# ESP32-SCH.net
KiCad netlist of a schematic drawn in Altium Designer
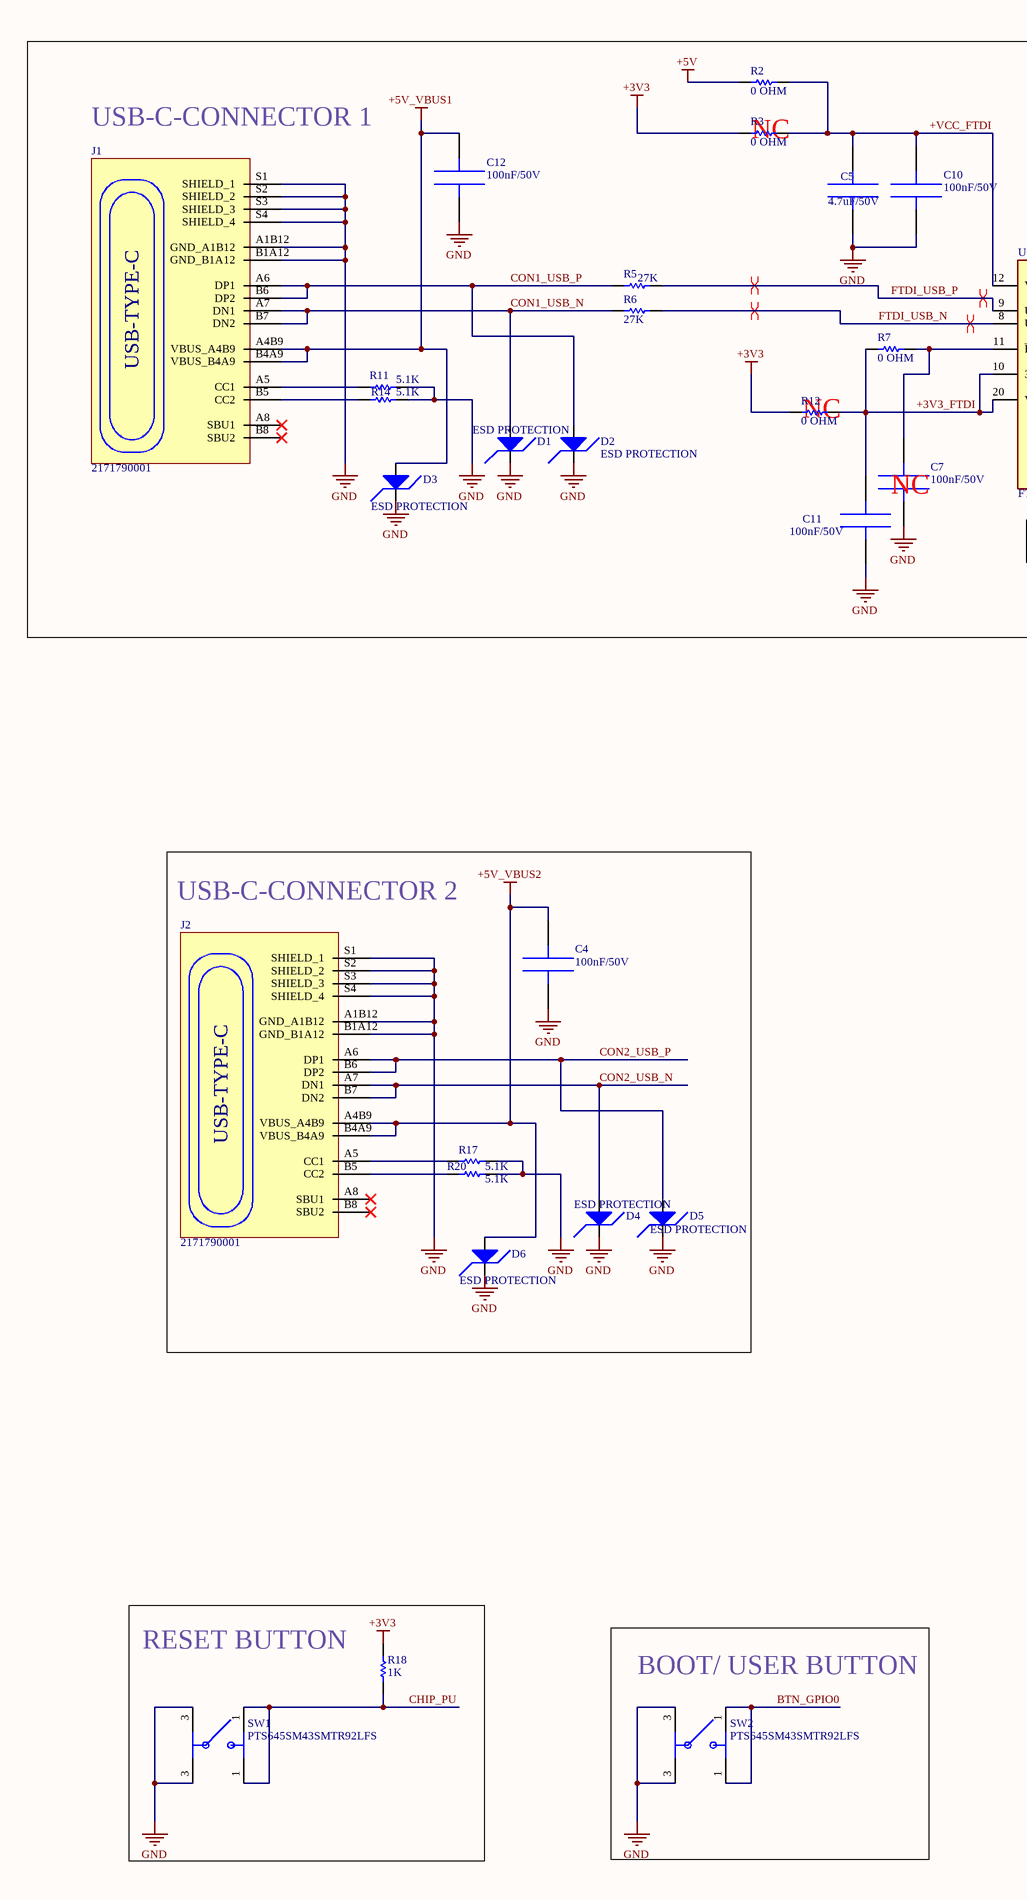
[diagram p0: ESP32-SCH.SchDoc, left]
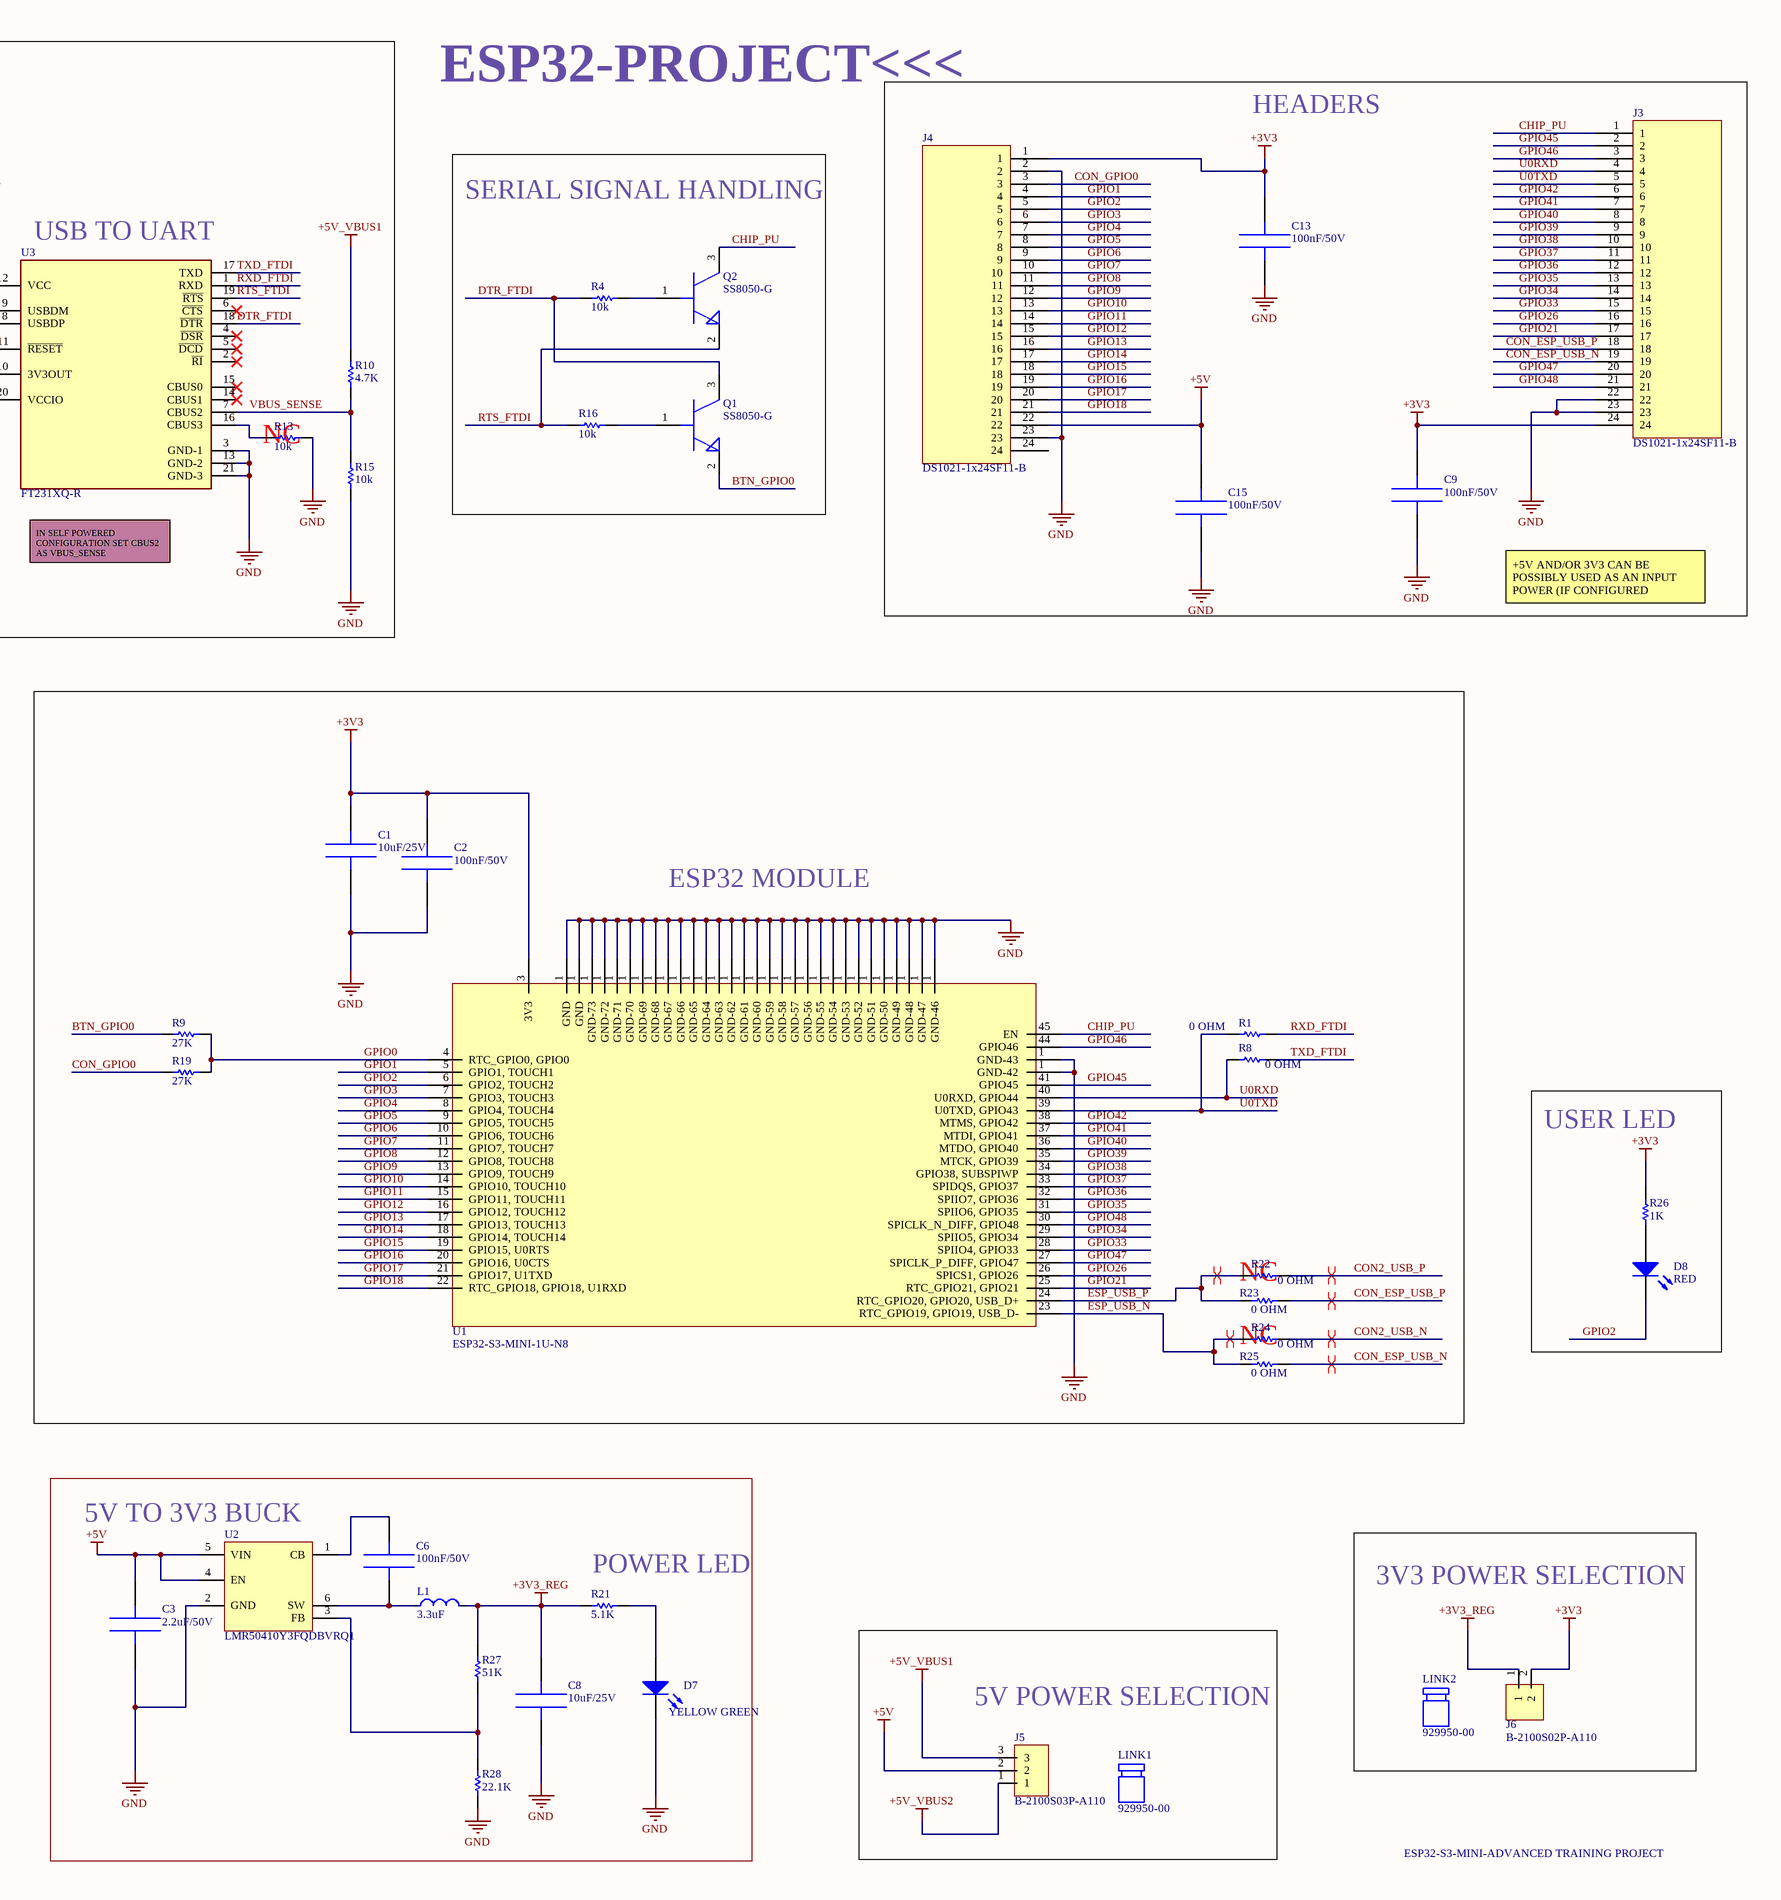
[diagram p1: ESP32-SCH.SchDoc, right]

(export (version "E")
  (design (tool "Eeschema 10.0.6"))
  (components
    (comp (ref "C1")
      (value "10uF/25V")
      (footprint "CL05A106MP8NUB8")
      (fields
        (field (name "MANUFACTURER") "Samsung")
        (field (name "MANUFACTURER PART NUMBER") "CL05A106MP8NUB8")
        (field (name "LCSC PART NUMBER") "C307415")
      )
      (libsource (lib "Schlib1") (part "CL05A106MP8NUB8"))
    )
    (comp (ref "C2")
      (value "100nF/50V")
      (footprint "CL05A106MP8NUB8")
      (fields
        (field (name "MANUFACTURER") "Samsung")
        (field (name "MANUFACTURER PART NUMBER") "CL10A105KP8NNNC")
        (field (name "LCSC PART NUMBER") "C14445")
      )
      (libsource (lib "Schlib1") (part "CL10A105KP8NNNC"))
    )
    (comp (ref "C3")
      (value "2.2uF/50V")
      (footprint "CL05A106MP8NUB8")
      (fields
        (field (name "MANUFACTURER") "Samsung")
        (field (name "MANUFACTURER PART NUMBER") "CL10A225KB8NNNC")
        (field (name "LCSC PART NUMBER") "C913904")
      )
      (libsource (lib "Schlib1") (part "CL10A225KB8NNNC"))
    )
    (comp (ref "C4")
      (value "100nF/50V")
      (footprint "CL05A106MP8NUB8")
      (fields
        (field (name "MANUFACTURER") "Samsung")
        (field (name "MANUFACTURER PART NUMBER") "CL10A105KP8NNNC")
        (field (name "LCSC PART NUMBER") "C14445")
      )
      (libsource (lib "Schlib1") (part "CL10A105KP8NNNC"))
    )
    (comp (ref "C5")
      (value "4.7uF/50V")
      (footprint "CC0603KRX7R9BB104")
      (fields
        (field (name "MANUFACTURER") "Yageo")
        (field (name "MANUFACTURER PART NUMBER") "CC0603KRX7R9BB104")
        (field (name "LCSC PART NUMBER") "C14663")
      )
      (libsource (lib "Schlib1") (part "CC0603KRX7R9BB104"))
    )
    (comp (ref "C6")
      (value "100nF/50V")
      (footprint "CL05A106MP8NUB8")
      (fields
        (field (name "MANUFACTURER") "Samsung")
        (field (name "MANUFACTURER PART NUMBER") "CL10A105KP8NNNC")
        (field (name "LCSC PART NUMBER") "C14445")
      )
      (libsource (lib "Schlib1") (part "CL10A105KP8NNNC"))
    )
    (comp (ref "C7")
      (value "100nF/50V")
      (footprint "CL05A106MP8NUB8")
      (fields
        (field (name "MANUFACTURER") "Samsung")
        (field (name "MANUFACTURER PART NUMBER") "CL10A105KP8NNNC")
        (field (name "LCSC PART NUMBER") "C14445")
      )
      (libsource (lib "Schlib1") (part "CL10A105KP8NNNC"))
    )
    (comp (ref "C8")
      (value "10uF/25V")
      (footprint "CL05A106MP8NUB8")
      (fields
        (field (name "MANUFACTURER") "Samsung")
        (field (name "MANUFACTURER PART NUMBER") "CL05A106MP8NUB8")
        (field (name "LCSC PART NUMBER") "C307415")
      )
      (libsource (lib "Schlib1") (part "CL05A106MP8NUB8"))
    )
    (comp (ref "C9")
      (value "100nF/50V")
      (footprint "CL05A106MP8NUB8")
      (fields
        (field (name "MANUFACTURER") "Samsung")
        (field (name "MANUFACTURER PART NUMBER") "CL10A105KP8NNNC")
        (field (name "LCSC PART NUMBER") "C14445")
      )
      (libsource (lib "Schlib1") (part "CL10A105KP8NNNC"))
    )
    (comp (ref "C10")
      (value "100nF/50V")
      (footprint "CL05A106MP8NUB8")
      (fields
        (field (name "MANUFACTURER") "Samsung")
        (field (name "MANUFACTURER PART NUMBER") "CL10A105KP8NNNC")
        (field (name "LCSC PART NUMBER") "C14445")
      )
      (libsource (lib "Schlib1") (part "CL10A105KP8NNNC"))
    )
    (comp (ref "C11")
      (value "100nF/50V")
      (footprint "CL05A106MP8NUB8")
      (fields
        (field (name "MANUFACTURER") "Samsung")
        (field (name "MANUFACTURER PART NUMBER") "CL10A105KP8NNNC")
        (field (name "LCSC PART NUMBER") "C14445")
      )
      (libsource (lib "Schlib1") (part "CL10A105KP8NNNC"))
    )
    (comp (ref "C12")
      (value "100nF/50V")
      (footprint "CL05A106MP8NUB8")
      (fields
        (field (name "MANUFACTURER") "Samsung")
        (field (name "MANUFACTURER PART NUMBER") "CL10A105KP8NNNC")
        (field (name "LCSC PART NUMBER") "C14445")
      )
      (libsource (lib "Schlib1") (part "CL10A105KP8NNNC"))
    )
    (comp (ref "C13")
      (value "100nF/50V")
      (footprint "CL05A106MP8NUB8")
      (fields
        (field (name "MANUFACTURER") "Samsung")
        (field (name "MANUFACTURER PART NUMBER") "CL10A105KP8NNNC")
        (field (name "LCSC PART NUMBER") "C14445")
      )
      (libsource (lib "Schlib1") (part "CL10A105KP8NNNC"))
    )
    (comp (ref "C15")
      (value "100nF/50V")
      (footprint "CL05A106MP8NUB8")
      (fields
        (field (name "MANUFACTURER") "Samsung")
        (field (name "MANUFACTURER PART NUMBER") "CL10A105KP8NNNC")
        (field (name "LCSC PART NUMBER") "C14445")
      )
      (libsource (lib "Schlib1") (part "CL10A105KP8NNNC"))
    )
    (comp (ref "D1")
      (value "ESD PROTECTION")
      (footprint "ESD5Z3.3T1G")
      (description "Trans Voltage Suppressor Diode, 158W, 3.3V V(RWM), Unidirectional, 1 Element, Silicon")
      (fields
        (field (name "MANUFACTURER") "ON Semiconductor")
        (field (name "MANUFACTURER PART NUMBER") "ESD5Z3.3T1G")
      )
      (libsource (lib "Schlib1") (part "ESD5Z3.3T1G"))
    )
    (comp (ref "D2")
      (value "ESD PROTECTION")
      (footprint "ESD5Z3.3T1G")
      (description "Trans Voltage Suppressor Diode, 158W, 3.3V V(RWM), Unidirectional, 1 Element, Silicon")
      (fields
        (field (name "MANUFACTURER") "ON Semiconductor")
        (field (name "MANUFACTURER PART NUMBER") "ESD5Z3.3T1G")
      )
      (libsource (lib "Schlib1") (part "ESD5Z3.3T1G"))
    )
    (comp (ref "D3")
      (value "ESD PROTECTION")
      (footprint "ESD5Z3.3T1G")
      (description "Trans Voltage Suppressor Diode, 158W, 3.3V V(RWM), Unidirectional, 1 Element, Silicon")
      (fields
        (field (name "MANUFACTURER") "ON Semiconductor")
        (field (name "MANUFACTURER PART NUMBER") "ESD5Z3.3T1G")
      )
      (libsource (lib "Schlib1") (part "ESD5Z3.3T1G"))
    )
    (comp (ref "D4")
      (value "ESD PROTECTION")
      (footprint "ESD5Z3.3T1G")
      (description "Trans Voltage Suppressor Diode, 158W, 3.3V V(RWM), Unidirectional, 1 Element, Silicon")
      (fields
        (field (name "MANUFACTURER") "ON Semiconductor")
        (field (name "MANUFACTURER PART NUMBER") "ESD5Z3.3T1G")
      )
      (libsource (lib "Schlib1") (part "ESD5Z3.3T1G"))
    )
    (comp (ref "D5")
      (value "ESD PROTECTION")
      (footprint "ESD5Z3.3T1G")
      (description "Trans Voltage Suppressor Diode, 158W, 3.3V V(RWM), Unidirectional, 1 Element, Silicon")
      (fields
        (field (name "MANUFACTURER") "ON Semiconductor")
        (field (name "MANUFACTURER PART NUMBER") "ESD5Z3.3T1G")
      )
      (libsource (lib "Schlib1") (part "ESD5Z3.3T1G"))
    )
    (comp (ref "D6")
      (value "ESD PROTECTION")
      (footprint "ESD5Z3.3T1G")
      (description "Trans Voltage Suppressor Diode, 158W, 3.3V V(RWM), Unidirectional, 1 Element, Silicon")
      (fields
        (field (name "MANUFACTURER") "ON Semiconductor")
        (field (name "MANUFACTURER PART NUMBER") "ESD5Z3.3T1G")
      )
      (libsource (lib "Schlib1") (part "ESD5Z3.3T1G"))
    )
    (comp (ref "D7")
      (value "YELLOW GREEN")
      (footprint "VLMG1500-GS08")
      (description "Single Color LED, Yellow Green, 0.5mm")
      (fields
        (field (name "MANUFACTURER") "Vishay")
        (field (name "MANUFACTURER PART NUMBER") "VLMG1500-GS08")
      )
      (libsource (lib "Schlib1") (part "VLMG1500-GS08"))
    )
    (comp (ref "D8")
      (value "RED")
      (footprint "VLMG1500-GS08")
      (description "Single Color LED, Super Red, 0.5mm")
      (fields
        (field (name "MANUFACTURER") "Vishay")
        (field (name "MANUFACTURER PART NUMBER") "VLMS1500-GS08")
      )
      (libsource (lib "Schlib1") (part "VLMS1500-GS08"))
    )
    (comp (ref "J1")
      (value "2171790001")
      (footprint "217179-0001")
      (description "USB Type C - Connector, Top-mount SMT, 16pos ¦ Molex Incorporated 217179-0001")
      (fields (field (name "MANUFACTURER") "Molex") (field (name "MANUFACTURER PART NUMBER") "217179-0001"))
      (libsource (lib "Schlib1") (part "217179-0001"))
    )
    (comp (ref "J2")
      (value "2171790001")
      (footprint "217179-0001")
      (description "USB Type C - Connector, Top-mount SMT, 16pos ¦ Molex Incorporated 217179-0001")
      (fields (field (name "MANUFACTURER") "Molex") (field (name "MANUFACTURER PART NUMBER") "217179-0001"))
      (libsource (lib "Schlib1") (part "217179-0001"))
    )
    (comp (ref "J3")
      (value "DS1021-1x24SF11-B")
      (footprint "DS1021-1x24SF11")
      (fields
        (field (name "MANUFACTURER") "Ningbo Connfly Electric")
        (field (name "LCSC PART NUMBER") "C7430380")
      )
      (libsource (lib "Schlib1") (part "DS1021-1x24SF11-B"))
    )
    (comp (ref "J4")
      (value "DS1021-1x24SF11-B")
      (footprint "DS1021-1x24SF11")
      (fields
        (field (name "MANUFACTURER") "Ningbo Connfly Electric")
        (field (name "LCSC PART NUMBER") "C7430380")
      )
      (libsource (lib "") (part "DS1021-1x24SF11-B_1"))
    )
    (comp (ref "J5")
      (value "B-2100S03P-A110")
      (footprint "B-2100S03P-A110")
      (fields (field (name "MANUFACTURER") "CKMTW") (field (name "LCSC PART NUMBER") "C124376"))
      (libsource (lib "Schlib1") (part "B-2100S03P-A110"))
    )
    (comp (ref "J6")
      (value "B-2100S02P-A110")
      (footprint "B-2100S02P-A110")
      (fields (field (name "MANUFACTURER") "CKMTW") (field (name "LCSC PART NUMBER") "C124375"))
      (libsource (lib "Schlib1") (part "B-2100S02P-A110"))
    )
    (comp (ref "L1")
      (value "3.3uF")
      (footprint "MLZ2012N3R3LT000")
      (description "General Purpose Inductor, 3.3uH, 20%, 1 Element, Ferrite-Core, SMD, 0805")
      (fields
        (field (name "MANUFACTURER") "TDK")
        (field (name "MANUFACTURER PART NUMBER") "MLZ2012N3R3LT000")
      )
      (libsource (lib "Schlib1") (part "MLZ2012N3R3LT000"))
    )
    (comp (ref "LINK1")
      (value "929950-00")
      (description "INTERCONNECTION DEVICE")
      (fields (field (name "MANUFACTURER") "3M") (field (name "LCSC PART NUMBER") "C6725179"))
      (libsource (lib "Schlib1") (part "929950-00"))
    )
    (comp (ref "LINK2")
      (value "929950-00")
      (description "INTERCONNECTION DEVICE")
      (fields (field (name "MANUFACTURER") "3M") (field (name "LCSC PART NUMBER") "C6725179"))
      (libsource (lib "Schlib1") (part "929950-00"))
    )
    (comp (ref "Q1")
      (value "SS8050-G")
      (footprint "SS8050-G")
      (description "Small Signal Bipolar Transistor, 1.5A I(C), 25V V(BR)CEO, 1-Element, NPN, Silicon")
      (fields (field (name "MANUFACTURER") "Comchip") (field (name "LCSC PART NUMBER") "C164885"))
      (libsource (lib "Schlib1") (part "SS8050-G"))
    )
    (comp (ref "Q2")
      (value "SS8050-G")
      (footprint "SS8050-G")
      (description "Small Signal Bipolar Transistor, 1.5A I(C), 25V V(BR)CEO, 1-Element, NPN, Silicon")
      (fields (field (name "MANUFACTURER") "Comchip") (field (name "LCSC PART NUMBER") "C164885"))
      (libsource (lib "Schlib1") (part "SS8050-G"))
    )
    (comp (ref "R1")
      (value "0 OHM")
      (footprint "RC0402JR")
      (description "Metal Glaze/thick Film, 0.0625W, 0ohm, Surface Mount, 0402")
      (fields
        (field (name "MANUFACTURER") "Yageo")
        (field (name "MANUFACTURER PART NUMBER") "RC0402JR-070RL")
      )
      (libsource (lib "Schlib1") (part "RC0402JR-070RL"))
    )
    (comp (ref "R2")
      (value "0 OHM")
      (footprint "RC0402JR")
      (description "Metal Glaze/thick Film, 0.0625W, 0ohm, Surface Mount, 0402")
      (fields
        (field (name "MANUFACTURER") "Yageo")
        (field (name "MANUFACTURER PART NUMBER") "RC0402JR-070RL")
      )
      (libsource (lib "Schlib1") (part "RC0402JR-070RL"))
    )
    (comp (ref "R3")
      (value "0 OHM")
      (footprint "RC0402JR")
      (description "Metal Glaze/thick Film, 0.0625W, 0ohm, Surface Mount, 0402")
      (fields
        (field (name "MANUFACTURER") "Yageo")
        (field (name "MANUFACTURER PART NUMBER") "RC0402JR-070RL")
      )
      (libsource (lib "Schlib1") (part "RC0402JR-070RL"))
    )
    (comp (ref "R4")
      (value "10k")
      (footprint "RC0402JR")
      (fields
        (field (name "MANUFACTURER") "Stackpole Electronics")
        (field (name "MANUFACTURER PART NUMBER") "RMCF0402FT10K0")
        (field (name "TOLERANCE") "1%")
      )
      (libsource (lib "Schlib1") (part "RMCF0402FT10K0"))
    )
    (comp (ref "R5")
      (value "27K")
      (footprint "RC0402JR")
      (fields
        (field (name "MANUFACTURER") "Yageo")
        (field (name "MANUFACTURER PART NUMBER") "RC0402JR-0727KL")
        (field (name "TOLERANCE") "5%")
      )
      (libsource (lib "Schlib1") (part "RC0402JR-0727KL"))
    )
    (comp (ref "R6")
      (value "27K")
      (footprint "RC0402JR")
      (fields
        (field (name "MANUFACTURER") "Yageo")
        (field (name "MANUFACTURER PART NUMBER") "RC0402JR-0727KL")
        (field (name "TOLERANCE") "5%")
      )
      (libsource (lib "Schlib1") (part "RC0402JR-0727KL"))
    )
    (comp (ref "R7")
      (value "0 OHM")
      (footprint "RC0402JR")
      (description "Metal Glaze/thick Film, 0.0625W, 0ohm, Surface Mount, 0402")
      (fields
        (field (name "MANUFACTURER") "Yageo")
        (field (name "MANUFACTURER PART NUMBER") "RC0402JR-070RL")
      )
      (libsource (lib "Schlib1") (part "RC0402JR-070RL"))
    )
    (comp (ref "R8")
      (value "0 OHM")
      (footprint "RC0402JR")
      (description "Metal Glaze/thick Film, 0.0625W, 0ohm, Surface Mount, 0402")
      (fields
        (field (name "MANUFACTURER") "Yageo")
        (field (name "MANUFACTURER PART NUMBER") "RC0402JR-070RL")
      )
      (libsource (lib "Schlib1") (part "RC0402JR-070RL"))
    )
    (comp (ref "R9")
      (value "27K")
      (footprint "RC0402JR")
      (fields
        (field (name "MANUFACTURER") "Yageo")
        (field (name "MANUFACTURER PART NUMBER") "RC0402JR-0727KL")
        (field (name "TOLERANCE") "5%")
      )
      (libsource (lib "Schlib1") (part "RC0402JR-0727KL"))
    )
    (comp (ref "R10")
      (value "4.7K")
      (footprint "RC0402JR")
      (fields
        (field (name "MANUFACTURER") "Yageo")
        (field (name "MANUFACTURER PART NUMBER") "RC0402JR-074K7L")
        (field (name "TOLERANCE") "5%")
      )
      (libsource (lib "Schlib1") (part "RC0402JR-074K7L"))
    )
    (comp (ref "R11")
      (value "5.1K")
      (footprint "AC0402FR-075K1L")
      (fields
        (field (name "MANUFACTURER") "Yageo")
        (field (name "MANUFACTURER PART NUMBER") "AC0402FR-075K1L")
        (field (name "TOLERANCE") "1%")
      )
      (libsource (lib "Schlib1") (part "AC0402FR-075K1L"))
    )
    (comp (ref "R12")
      (value "0 OHM")
      (footprint "RC0402JR")
      (description "Metal Glaze/thick Film, 0.0625W, 0ohm, Surface Mount, 0402")
      (fields
        (field (name "MANUFACTURER") "Yageo")
        (field (name "MANUFACTURER PART NUMBER") "RC0402JR-070RL")
      )
      (libsource (lib "Schlib1") (part "RC0402JR-070RL"))
    )
    (comp (ref "R13")
      (value "10k")
      (footprint "RC0402JR")
      (fields
        (field (name "MANUFACTURER") "Stackpole Electronics")
        (field (name "MANUFACTURER PART NUMBER") "RMCF0402FT10K0")
        (field (name "TOLERANCE") "1%")
      )
      (libsource (lib "Schlib1") (part "RMCF0402FT10K0"))
    )
    (comp (ref "R14")
      (value "5.1K")
      (footprint "AC0402FR-075K1L")
      (fields
        (field (name "MANUFACTURER") "Yageo")
        (field (name "MANUFACTURER PART NUMBER") "AC0402FR-075K1L")
        (field (name "TOLERANCE") "1%")
      )
      (libsource (lib "Schlib1") (part "AC0402FR-075K1L"))
    )
    (comp (ref "R15")
      (value "10k")
      (footprint "RC0402JR")
      (fields
        (field (name "MANUFACTURER") "Stackpole Electronics")
        (field (name "MANUFACTURER PART NUMBER") "RMCF0402FT10K0")
        (field (name "TOLERANCE") "1%")
      )
      (libsource (lib "Schlib1") (part "RMCF0402FT10K0"))
    )
    (comp (ref "R16")
      (value "10k")
      (footprint "RC0402JR")
      (fields
        (field (name "MANUFACTURER") "Stackpole Electronics")
        (field (name "MANUFACTURER PART NUMBER") "RMCF0402FT10K0")
        (field (name "TOLERANCE") "1%")
      )
      (libsource (lib "Schlib1") (part "RMCF0402FT10K0"))
    )
    (comp (ref "R17")
      (value "5.1K")
      (footprint "AC0402FR-075K1L")
      (fields
        (field (name "MANUFACTURER") "Yageo")
        (field (name "MANUFACTURER PART NUMBER") "AC0402FR-075K1L")
        (field (name "TOLERANCE") "1%")
      )
      (libsource (lib "Schlib1") (part "AC0402FR-075K1L"))
    )
    (comp (ref "R18")
      (value "1K")
      (footprint "0603WAF1001T5E")
      (fields
        (field (name "MANUFACTURER") "Royal Electronic Factory")
        (field (name "MANUFACTURER PART NUMBER") "0603WAF1001T5E")
        (field (name "LCSC PART NUMBER") "C21190")
      )
      (libsource (lib "Schlib1") (part "0603WAF1001T5E"))
    )
    (comp (ref "R19")
      (value "27K")
      (footprint "RC0402JR")
      (fields
        (field (name "MANUFACTURER") "Yageo")
        (field (name "MANUFACTURER PART NUMBER") "RC0402JR-0727KL")
        (field (name "TOLERANCE") "5%")
      )
      (libsource (lib "Schlib1") (part "RC0402JR-0727KL"))
    )
    (comp (ref "R20")
      (value "5.1K")
      (footprint "AC0402FR-075K1L")
      (fields
        (field (name "MANUFACTURER") "Yageo")
        (field (name "MANUFACTURER PART NUMBER") "AC0402FR-075K1L")
        (field (name "TOLERANCE") "1%")
      )
      (libsource (lib "Schlib1") (part "AC0402FR-075K1L"))
    )
    (comp (ref "R21")
      (value "5.1K")
      (footprint "AC0402FR-075K1L")
      (fields
        (field (name "MANUFACTURER") "Yageo")
        (field (name "MANUFACTURER PART NUMBER") "AC0402FR-075K1L")
        (field (name "TOLERANCE") "1%")
      )
      (libsource (lib "Schlib1") (part "AC0402FR-075K1L"))
    )
    (comp (ref "R22")
      (value "0 OHM")
      (footprint "RC0402JR")
      (description "Metal Glaze/thick Film, 0.0625W, 0ohm, Surface Mount, 0402")
      (fields
        (field (name "MANUFACTURER") "Yageo")
        (field (name "MANUFACTURER PART NUMBER") "RC0402JR-070RL")
      )
      (libsource (lib "Schlib1") (part "RC0402JR-070RL"))
    )
    (comp (ref "R23")
      (value "0 OHM")
      (footprint "RC0402JR")
      (description "Metal Glaze/thick Film, 0.0625W, 0ohm, Surface Mount, 0402")
      (fields
        (field (name "MANUFACTURER") "Yageo")
        (field (name "MANUFACTURER PART NUMBER") "RC0402JR-070RL")
      )
      (libsource (lib "Schlib1") (part "RC0402JR-070RL"))
    )
    (comp (ref "R24")
      (value "0 OHM")
      (footprint "RC0402JR")
      (description "Metal Glaze/thick Film, 0.0625W, 0ohm, Surface Mount, 0402")
      (fields
        (field (name "MANUFACTURER") "Yageo")
        (field (name "MANUFACTURER PART NUMBER") "RC0402JR-070RL")
      )
      (libsource (lib "Schlib1") (part "RC0402JR-070RL"))
    )
    (comp (ref "R25")
      (value "0 OHM")
      (footprint "RC0402JR")
      (description "Metal Glaze/thick Film, 0.0625W, 0ohm, Surface Mount, 0402")
      (fields
        (field (name "MANUFACTURER") "Yageo")
        (field (name "MANUFACTURER PART NUMBER") "RC0402JR-070RL")
      )
      (libsource (lib "Schlib1") (part "RC0402JR-070RL"))
    )
    (comp (ref "R26")
      (value "1K")
      (footprint "0603WAF1001T5E")
      (fields
        (field (name "MANUFACTURER") "Royal Electronic Factory")
        (field (name "MANUFACTURER PART NUMBER") "0603WAF1001T5E")
        (field (name "LCSC PART NUMBER") "C21190")
      )
      (libsource (lib "Schlib1") (part "0603WAF1001T5E"))
    )
    (comp (ref "R27")
      (value "51K")
      (footprint "RC0402JR")
      (fields
        (field (name "MANUFACTURER") "Yageo")
        (field (name "MANUFACTURER PART NUMBER") "RC0402FR-0751KL")
        (field (name "TOLERANCE") "1%")
      )
      (libsource (lib "Schlib1") (part "RC0402FR-0751KL"))
    )
    (comp (ref "R28")
      (value "22.1K")
      (footprint "RC0402JR")
      (fields
        (field (name "MANUFACTURER") "Yageo")
        (field (name "MANUFACTURER PART NUMBER") "RC0402FR-0722K1L")
        (field (name "TOLERANCE") "1%")
      )
      (libsource (lib "Schlib1") (part "RC0402FR-0722K1L"))
    )
    (comp (ref "SW1")
      (value "PTS645SM43SMTR92LFS")
      (footprint "PTS645SM43SMTR92LFS")
      (fields (field (name "MANUFACTURER") "ITT C&K") (field (name "LCSC PART NUMBER") "C221880"))
      (libsource (lib "Schlib1") (part "PTS645SM43SMTR92LFS"))
    )
    (comp (ref "SW2")
      (value "PTS645SM43SMTR92LFS")
      (footprint "PTS645SM43SMTR92LFS")
      (fields (field (name "MANUFACTURER") "ITT C&K") (field (name "LCSC PART NUMBER") "C221880"))
      (libsource (lib "Schlib1") (part "PTS645SM43SMTR92LFS"))
    )
    (comp (ref "U1")
      (value "ESP32-S3-MINI-1U-N8")
      (footprint "ESP32-S3-MINI-1U-N8_1")
      (fields (field (name "MANUFACTURER") "Espressif Systems") (field (name "LCSC PART NUMBER") "C2980299"))
      (libsource (lib "Schlib1") (part "ESP32-S3-MINI-1U-N8_1"))
    )
    (comp (ref "U2")
      (value "LMR50410Y3FQDBVRQ1")
      (footprint "LMR50410Y3FQDBVRQ1")
      (description "Switching Regulator, Current-mode, 1A, 2100kHz Switching Freq-Max, PDSO6")
      (fields (field (name "MANUFACTURER") "Texas Instruments") (field (name "LCSC PART NUMBER") "C5219374"))
      (libsource (lib "Schlib1") (part "LMR50410Y3FQDBVRQ1"))
    )
    (comp (ref "U3")
      (value "FT231XQ-R")
      (footprint "FT231XQ-R")
      (description "Microprocessor Circuit, CMOS")
      (fields (field (name "MANUFACTURER") "FTDI") (field (name "LCSC PART NUMBER") "C132159"))
      (libsource (lib "Schlib1") (part "FT231XQ-R"))
    )
  )
  (nets
    (net (code "1") (name "+3V3") (class "Default")
      (node (ref "C1") (pin "2") (pinfunction "2_2") (pintype "passive"))
      (node (ref "C13") (pin "2") (pinfunction "2_2") (pintype "passive"))
      (node (ref "C2") (pin "2") (pinfunction "2_2") (pintype "passive"))
      (node (ref "C9") (pin "2") (pinfunction "2_2") (pintype "passive"))
      (node (ref "J3") (pin "24") (pinfunction "24_24") (pintype "passive"))
      (node (ref "J4") (pin "1") (pinfunction "1_1") (pintype "passive"))
      (node (ref "J6") (pin "2") (pinfunction "2_2") (pintype "passive"))
      (node (ref "R12") (pin "1") (pinfunction "1_1") (pintype "passive"))
      (node (ref "R18") (pin "2") (pinfunction "2_2") (pintype "passive"))
      (node (ref "R26") (pin "2") (pinfunction "2_2") (pintype "passive"))
      (node (ref "R3") (pin "1") (pinfunction "1_1") (pintype "passive"))
      (node (ref "U1") (pin "3") (pinfunction "3V3_3") (pintype "passive"))
    )
    (net (code "2") (name "+3V3_REG") (class "Default")
      (node (ref "C8") (pin "2") (pinfunction "2_2") (pintype "passive"))
      (node (ref "J6") (pin "1") (pinfunction "1_1") (pintype "passive"))
      (node (ref "L1") (pin "2") (pinfunction "2_2") (pintype "passive"))
      (node (ref "R21") (pin "1") (pinfunction "1_1") (pintype "passive"))
      (node (ref "R27") (pin "2") (pinfunction "2_2") (pintype "passive"))
    )
    (net (code "3") (name "+5V") (class "Default")
      (node (ref "C15") (pin "2") (pinfunction "2_2") (pintype "passive"))
      (node (ref "C3") (pin "1") (pinfunction "1_1") (pintype "passive"))
      (node (ref "J4") (pin "22") (pinfunction "22_22") (pintype "passive"))
      (node (ref "J5") (pin "2") (pinfunction "2_2") (pintype "passive"))
      (node (ref "R2") (pin "1") (pinfunction "1_1") (pintype "passive"))
      (node (ref "U2") (pin "4") (pinfunction "EN_4") (pintype "passive"))
      (node (ref "U2") (pin "5") (pinfunction "VIN_5") (pintype "passive"))
    )
    (net (code "4") (name "+5V_VBUS1") (class "Default")
      (node (ref "C12") (pin "2") (pinfunction "2_2") (pintype "passive"))
      (node (ref "D3") (pin "2") (pinfunction "2_2") (pintype "passive"))
      (node (ref "J1") (pin "A4B9") (pinfunction "VBUS_A4B9_A4B9") (pintype "passive"))
      (node (ref "J1") (pin "B4A9") (pinfunction "VBUS_B4A9_B4A9") (pintype "passive"))
      (node (ref "J5") (pin "3") (pinfunction "3_3") (pintype "passive"))
      (node (ref "R10") (pin "2") (pinfunction "2_2") (pintype "passive"))
    )
    (net (code "5") (name "+5V_VBUS2") (class "Default")
      (node (ref "C4") (pin "2") (pinfunction "2_2") (pintype "passive"))
      (node (ref "D6") (pin "2") (pinfunction "2_2") (pintype "passive"))
      (node (ref "J2") (pin "A4B9") (pinfunction "VBUS_A4B9_A4B9") (pintype "passive"))
      (node (ref "J2") (pin "B4A9") (pinfunction "VBUS_B4A9_B4A9") (pintype "passive"))
      (node (ref "J5") (pin "1") (pinfunction "1_1") (pintype "passive"))
    )
    (net (code "6") (name "/+3V3_FTDI") (class "Default")
      (node (ref "C11") (pin "2") (pinfunction "2_2") (pintype "passive"))
      (node (ref "R12") (pin "2") (pinfunction "2_2") (pintype "passive"))
      (node (ref "R7") (pin "1") (pinfunction "1_1") (pintype "passive"))
      (node (ref "U3") (pin "10") (pinfunction "3V3OUT_10") (pintype "passive"))
      (node (ref "U3") (pin "20") (pinfunction "VCCIO_20") (pintype "power_in"))
    )
    (net (code "7") (name "/+VCC_FTDI") (class "Default")
      (node (ref "C10") (pin "2") (pinfunction "2_2") (pintype "passive"))
      (node (ref "C5") (pin "2") (pinfunction "2_2") (pintype "passive"))
      (node (ref "R2") (pin "2") (pinfunction "2_2") (pintype "passive"))
      (node (ref "R3") (pin "2") (pinfunction "2_2") (pintype "passive"))
      (node (ref "U3") (pin "12") (pinfunction "VCC_12") (pintype "power_in"))
    )
    (net (code "8") (name "/BTN_GPIO0") (class "Default")
      (node (ref "Q1") (pin "2") (pinfunction "E_2") (pintype "passive"))
      (node (ref "R9") (pin "1") (pinfunction "1_1") (pintype "passive"))
      (node (ref "SW2") (pin "1") (pinfunction "1_1") (pintype "passive"))
    )
    (net (code "9") (name "/CHIP_PU") (class "Default")
      (node (ref "J3") (pin "1") (pinfunction "1_1") (pintype "passive"))
      (node (ref "Q2") (pin "3") (pinfunction "C_3") (pintype "passive"))
      (node (ref "R18") (pin "1") (pinfunction "1_1") (pintype "passive"))
      (node (ref "SW1") (pin "1") (pinfunction "1_1") (pintype "passive"))
      (node (ref "U1") (pin "45") (pinfunction "EN_45") (pintype "passive"))
    )
    (net (code "10") (name "/CON1_USB_N") (class "Default")
      (node (ref "D1") (pin "2") (pinfunction "2_2") (pintype "passive"))
      (node (ref "J1") (pin "A7") (pinfunction "DN1_A7") (pintype "passive"))
      (node (ref "J1") (pin "B7") (pinfunction "DN2_B7") (pintype "passive"))
      (node (ref "R6") (pin "1") (pinfunction "1_1") (pintype "passive"))
    )
    (net (code "11") (name "/CON1_USB_P") (class "Default")
      (node (ref "D2") (pin "2") (pinfunction "2_2") (pintype "passive"))
      (node (ref "J1") (pin "A6") (pinfunction "DP1_A6") (pintype "passive"))
      (node (ref "J1") (pin "B6") (pinfunction "DP2_B6") (pintype "passive"))
      (node (ref "R5") (pin "1") (pinfunction "1_1") (pintype "passive"))
    )
    (net (code "12") (name "/CON2_USB_N") (class "Default")
      (node (ref "D4") (pin "2") (pinfunction "2_2") (pintype "passive"))
      (node (ref "J2") (pin "A7") (pinfunction "DN1_A7") (pintype "passive"))
      (node (ref "J2") (pin "B7") (pinfunction "DN2_B7") (pintype "passive"))
      (node (ref "R24") (pin "2") (pinfunction "2_2") (pintype "passive"))
    )
    (net (code "13") (name "/CON2_USB_P") (class "Default")
      (node (ref "D5") (pin "2") (pinfunction "2_2") (pintype "passive"))
      (node (ref "J2") (pin "A6") (pinfunction "DP1_A6") (pintype "passive"))
      (node (ref "J2") (pin "B6") (pinfunction "DP2_B6") (pintype "passive"))
      (node (ref "R22") (pin "2") (pinfunction "2_2") (pintype "passive"))
    )
    (net (code "14") (name "/CON_ESP_USB_N") (class "Default")
      (node (ref "J3") (pin "19") (pinfunction "19_19") (pintype "passive"))
      (node (ref "R25") (pin "2") (pinfunction "2_2") (pintype "passive"))
    )
    (net (code "15") (name "/CON_ESP_USB_P") (class "Default")
      (node (ref "J3") (pin "18") (pinfunction "18_18") (pintype "passive"))
      (node (ref "R23") (pin "2") (pinfunction "2_2") (pintype "passive"))
    )
    (net (code "16") (name "/CON_GPIO0") (class "Default")
      (node (ref "J4") (pin "3") (pinfunction "3_3") (pintype "passive"))
      (node (ref "R19") (pin "1") (pinfunction "1_1") (pintype "passive"))
    )
    (net (code "17") (name "/DTR_FTDI") (class "Default")
      (node (ref "Q1") (pin "3") (pinfunction "C_3") (pintype "passive"))
      (node (ref "R4") (pin "1") (pinfunction "1_1") (pintype "passive"))
      (node (ref "U3") (pin "18") (pinfunction "~{DTR}_18") (pintype "passive"))
    )
    (net (code "18") (name "/ESP_USB_N") (class "Default")
      (node (ref "R24") (pin "1") (pinfunction "1_1") (pintype "passive"))
      (node (ref "R25") (pin "1") (pinfunction "1_1") (pintype "passive"))
      (node (ref "U1") (pin "23") (pinfunction "RTC_GPIO19,_GPIO19,_USB_D-_23") (pintype "passive"))
    )
    (net (code "19") (name "/ESP_USB_P") (class "Default")
      (node (ref "R22") (pin "1") (pinfunction "1_1") (pintype "passive"))
      (node (ref "R23") (pin "1") (pinfunction "1_1") (pintype "passive"))
      (node (ref "U1") (pin "24") (pinfunction "RTC_GPIO20,_GPIO20,_USB_D+_24") (pintype "passive"))
    )
    (net (code "20") (name "/FTDI_USB_N") (class "Default")
      (node (ref "R6") (pin "2") (pinfunction "2_2") (pintype "passive"))
      (node (ref "U3") (pin "8") (pinfunction "USBDP_8") (pintype "passive"))
    )
    (net (code "21") (name "/FTDI_USB_P") (class "Default")
      (node (ref "R5") (pin "2") (pinfunction "2_2") (pintype "passive"))
      (node (ref "U3") (pin "9") (pinfunction "USBDM_9") (pintype "passive"))
    )
    (net (code "22") (name "/GPIO0") (class "Default")
      (node (ref "R19") (pin "2") (pinfunction "2_2") (pintype "passive"))
      (node (ref "R9") (pin "2") (pinfunction "2_2") (pintype "passive"))
      (node (ref "U1") (pin "4") (pinfunction "RTC_GPIO0,_GPIO0_4") (pintype "passive"))
    )
    (net (code "23") (name "/GPIO1") (class "Default")
      (node (ref "J4") (pin "4") (pinfunction "4_4") (pintype "passive"))
      (node (ref "U1") (pin "5") (pinfunction "GPIO1,_TOUCH1_5") (pintype "passive"))
    )
    (net (code "24") (name "/GPIO2") (class "Default")
      (node (ref "D8") (pin "2") (pinfunction "2_2") (pintype "passive"))
      (node (ref "J4") (pin "5") (pinfunction "5_5") (pintype "passive"))
      (node (ref "U1") (pin "6") (pinfunction "GPIO2,_TOUCH2_6") (pintype "passive"))
    )
    (net (code "25") (name "/GPIO3") (class "Default")
      (node (ref "J4") (pin "6") (pinfunction "6_6") (pintype "passive"))
      (node (ref "U1") (pin "7") (pinfunction "GPIO3,_TOUCH3_7") (pintype "passive"))
    )
    (net (code "26") (name "/GPIO4") (class "Default")
      (node (ref "J4") (pin "7") (pinfunction "7_7") (pintype "passive"))
      (node (ref "U1") (pin "8") (pinfunction "GPIO4,_TOUCH4_8") (pintype "passive"))
    )
    (net (code "27") (name "/GPIO5") (class "Default")
      (node (ref "J4") (pin "8") (pinfunction "8_8") (pintype "passive"))
      (node (ref "U1") (pin "9") (pinfunction "GPIO5,_TOUCH5_9") (pintype "passive"))
    )
    (net (code "28") (name "/GPIO6") (class "Default")
      (node (ref "J4") (pin "9") (pinfunction "9_9") (pintype "passive"))
      (node (ref "U1") (pin "10") (pinfunction "GPIO6,_TOUCH6_10") (pintype "passive"))
    )
    (net (code "29") (name "/GPIO7") (class "Default")
      (node (ref "J4") (pin "10") (pinfunction "10_10") (pintype "passive"))
      (node (ref "U1") (pin "11") (pinfunction "GPIO7,_TOUCH7_11") (pintype "passive"))
    )
    (net (code "30") (name "/GPIO8") (class "Default")
      (node (ref "J4") (pin "11") (pinfunction "11_11") (pintype "passive"))
      (node (ref "U1") (pin "12") (pinfunction "GPIO8,_TOUCH8_12") (pintype "passive"))
    )
    (net (code "31") (name "/GPIO9") (class "Default")
      (node (ref "J4") (pin "12") (pinfunction "12_12") (pintype "passive"))
      (node (ref "U1") (pin "13") (pinfunction "GPIO9,_TOUCH9_13") (pintype "passive"))
    )
    (net (code "32") (name "/GPIO10") (class "Default")
      (node (ref "J4") (pin "13") (pinfunction "13_13") (pintype "passive"))
      (node (ref "U1") (pin "14") (pinfunction "GPIO10,_TOUCH10_14") (pintype "passive"))
    )
    (net (code "33") (name "/GPIO11") (class "Default")
      (node (ref "J4") (pin "14") (pinfunction "14_14") (pintype "passive"))
      (node (ref "U1") (pin "15") (pinfunction "GPIO11,_TOUCH11_15") (pintype "passive"))
    )
    (net (code "34") (name "/GPIO12") (class "Default")
      (node (ref "J4") (pin "15") (pinfunction "15_15") (pintype "passive"))
      (node (ref "U1") (pin "16") (pinfunction "GPIO12,_TOUCH12_16") (pintype "passive"))
    )
    (net (code "35") (name "/GPIO13") (class "Default")
      (node (ref "J4") (pin "16") (pinfunction "16_16") (pintype "passive"))
      (node (ref "U1") (pin "17") (pinfunction "GPIO13,_TOUCH13_17") (pintype "passive"))
    )
    (net (code "36") (name "/GPIO14") (class "Default")
      (node (ref "J4") (pin "17") (pinfunction "17_17") (pintype "passive"))
      (node (ref "U1") (pin "18") (pinfunction "GPIO14,_TOUCH14_18") (pintype "passive"))
    )
    (net (code "37") (name "/GPIO15") (class "Default")
      (node (ref "J4") (pin "18") (pinfunction "18_18") (pintype "passive"))
      (node (ref "U1") (pin "19") (pinfunction "GPIO15,_U0RTS_19") (pintype "passive"))
    )
    (net (code "38") (name "/GPIO16") (class "Default")
      (node (ref "J4") (pin "19") (pinfunction "19_19") (pintype "passive"))
      (node (ref "U1") (pin "20") (pinfunction "GPIO16,_U0CTS_20") (pintype "passive"))
    )
    (net (code "39") (name "/GPIO17") (class "Default")
      (node (ref "J4") (pin "20") (pinfunction "20_20") (pintype "passive"))
      (node (ref "U1") (pin "21") (pinfunction "GPIO17,_U1TXD_21") (pintype "passive"))
    )
    (net (code "40") (name "/GPIO18") (class "Default")
      (node (ref "J4") (pin "21") (pinfunction "21_21") (pintype "passive"))
      (node (ref "U1") (pin "22") (pinfunction "RTC_GPIO18,_GPIO18,_U1RXD_22") (pintype "passive"))
    )
    (net (code "41") (name "/GPIO21") (class "Default")
      (node (ref "J3") (pin "17") (pinfunction "17_17") (pintype "passive"))
      (node (ref "U1") (pin "25") (pinfunction "RTC_GPIO21,_GPIO21_25") (pintype "passive"))
    )
    (net (code "42") (name "/GPIO26") (class "Default")
      (node (ref "J3") (pin "16") (pinfunction "16_16") (pintype "passive"))
      (node (ref "U1") (pin "26") (pinfunction "SPICS1,_GPIO26_26") (pintype "passive"))
    )
    (net (code "43") (name "/GPIO33") (class "Default")
      (node (ref "J3") (pin "15") (pinfunction "15_15") (pintype "passive"))
      (node (ref "U1") (pin "28") (pinfunction "SPIIO4,_GPIO33_28") (pintype "passive"))
    )
    (net (code "44") (name "/GPIO34") (class "Default")
      (node (ref "J3") (pin "14") (pinfunction "14_14") (pintype "passive"))
      (node (ref "U1") (pin "29") (pinfunction "SPIIO5,_GPIO34_29") (pintype "passive"))
    )
    (net (code "45") (name "/GPIO35") (class "Default")
      (node (ref "J3") (pin "13") (pinfunction "13_13") (pintype "passive"))
      (node (ref "U1") (pin "31") (pinfunction "SPIIO6,_GPIO35_31") (pintype "passive"))
    )
    (net (code "46") (name "/GPIO36") (class "Default")
      (node (ref "J3") (pin "12") (pinfunction "12_12") (pintype "passive"))
      (node (ref "U1") (pin "32") (pinfunction "SPIIO7,_GPIO36_32") (pintype "passive"))
    )
    (net (code "47") (name "/GPIO37") (class "Default")
      (node (ref "J3") (pin "11") (pinfunction "11_11") (pintype "passive"))
      (node (ref "U1") (pin "33") (pinfunction "SPIDQS,_GPIO37_33") (pintype "passive"))
    )
    (net (code "48") (name "/GPIO38") (class "Default")
      (node (ref "J3") (pin "10") (pinfunction "10_10") (pintype "passive"))
      (node (ref "U1") (pin "34") (pinfunction "GPIO38,_SUBSPIWP_34") (pintype "passive"))
    )
    (net (code "49") (name "/GPIO39") (class "Default")
      (node (ref "J3") (pin "9") (pinfunction "9_9") (pintype "passive"))
      (node (ref "U1") (pin "35") (pinfunction "MTCK,_GPIO39_35") (pintype "passive"))
    )
    (net (code "50") (name "/GPIO40") (class "Default")
      (node (ref "J3") (pin "8") (pinfunction "8_8") (pintype "passive"))
      (node (ref "U1") (pin "36") (pinfunction "MTDO,_GPIO40_36") (pintype "passive"))
    )
    (net (code "51") (name "/GPIO41") (class "Default")
      (node (ref "J3") (pin "7") (pinfunction "7_7") (pintype "passive"))
      (node (ref "U1") (pin "37") (pinfunction "MTDI,_GPIO41_37") (pintype "passive"))
    )
    (net (code "52") (name "/GPIO42") (class "Default")
      (node (ref "J3") (pin "6") (pinfunction "6_6") (pintype "passive"))
      (node (ref "U1") (pin "38") (pinfunction "MTMS,_GPIO42_38") (pintype "passive"))
    )
    (net (code "53") (name "/GPIO45") (class "Default")
      (node (ref "J3") (pin "2") (pinfunction "2_2") (pintype "passive"))
      (node (ref "U1") (pin "41") (pinfunction "GPIO45_41") (pintype "passive"))
    )
    (net (code "54") (name "/GPIO46") (class "Default")
      (node (ref "J3") (pin "3") (pinfunction "3_3") (pintype "passive"))
      (node (ref "U1") (pin "44") (pinfunction "GPIO46_44") (pintype "passive"))
    )
    (net (code "55") (name "/GPIO47") (class "Default")
      (node (ref "J3") (pin "20") (pinfunction "20_20") (pintype "passive"))
      (node (ref "U1") (pin "27") (pinfunction "SPICLK_P_DIFF,_GPIO47_27") (pintype "passive"))
    )
    (net (code "56") (name "/GPIO48") (class "Default")
      (node (ref "J3") (pin "21") (pinfunction "21_21") (pintype "passive"))
      (node (ref "U1") (pin "30") (pinfunction "SPICLK_N_DIFF,_GPIO48_30") (pintype "passive"))
    )
    (net (code "57") (name "/RTS_FTDI") (class "Default")
      (node (ref "Q2") (pin "2") (pinfunction "E_2") (pintype "passive"))
      (node (ref "R16") (pin "1") (pinfunction "1_1") (pintype "passive"))
      (node (ref "U3") (pin "19") (pinfunction "~{RTS}_19") (pintype "passive"))
    )
    (net (code "58") (name "/RXD_FTDI") (class "Default")
      (node (ref "R1") (pin "2") (pinfunction "2_2") (pintype "passive"))
      (node (ref "U3") (pin "1") (pinfunction "RXD_1") (pintype "passive"))
    )
    (net (code "59") (name "/TXD_FTDI") (class "Default")
      (node (ref "R8") (pin "2") (pinfunction "2_2") (pintype "passive"))
      (node (ref "U3") (pin "17") (pinfunction "TXD_17") (pintype "passive"))
    )
    (net (code "60") (name "/U0RXD") (class "Default")
      (node (ref "J3") (pin "4") (pinfunction "4_4") (pintype "passive"))
      (node (ref "R8") (pin "1") (pinfunction "1_1") (pintype "passive"))
      (node (ref "U1") (pin "40") (pinfunction "U0RXD,_GPIO44_40") (pintype "passive"))
    )
    (net (code "61") (name "/U0TXD") (class "Default")
      (node (ref "J3") (pin "5") (pinfunction "5_5") (pintype "passive"))
      (node (ref "R1") (pin "1") (pinfunction "1_1") (pintype "passive"))
      (node (ref "U1") (pin "39") (pinfunction "U0TXD,_GPIO43_39") (pintype "passive"))
    )
    (net (code "62") (name "/VBUS_SENSE") (class "Default")
      (node (ref "R10") (pin "1") (pinfunction "1_1") (pintype "passive"))
      (node (ref "R15") (pin "2") (pinfunction "2_2") (pintype "passive"))
      (node (ref "U3") (pin "7") (pinfunction "CBUS2_7") (pintype "passive"))
    )
    (net (code "63") (name "GND") (class "Default")
      (node (ref "C1") (pin "1") (pinfunction "1_1") (pintype "passive"))
      (node (ref "C10") (pin "1") (pinfunction "1_1") (pintype "passive"))
      (node (ref "C11") (pin "1") (pinfunction "1_1") (pintype "passive"))
      (node (ref "C12") (pin "1") (pinfunction "1_1") (pintype "passive"))
      (node (ref "C13") (pin "1") (pinfunction "1_1") (pintype "passive"))
      (node (ref "C15") (pin "1") (pinfunction "1_1") (pintype "passive"))
      (node (ref "C2") (pin "1") (pinfunction "1_1") (pintype "passive"))
      (node (ref "C3") (pin "2") (pinfunction "2_2") (pintype "passive"))
      (node (ref "C4") (pin "1") (pinfunction "1_1") (pintype "passive"))
      (node (ref "C5") (pin "1") (pinfunction "1_1") (pintype "passive"))
      (node (ref "C7") (pin "1") (pinfunction "1_1") (pintype "passive"))
      (node (ref "C8") (pin "1") (pinfunction "1_1") (pintype "passive"))
      (node (ref "C9") (pin "1") (pinfunction "1_1") (pintype "passive"))
      (node (ref "D1") (pin "1") (pinfunction "1_1") (pintype "passive"))
      (node (ref "D2") (pin "1") (pinfunction "1_1") (pintype "passive"))
      (node (ref "D3") (pin "1") (pinfunction "1_1") (pintype "passive"))
      (node (ref "D4") (pin "1") (pinfunction "1_1") (pintype "passive"))
      (node (ref "D5") (pin "1") (pinfunction "1_1") (pintype "passive"))
      (node (ref "D6") (pin "1") (pinfunction "1_1") (pintype "passive"))
      (node (ref "D7") (pin "2") (pinfunction "2_2") (pintype "passive"))
      (node (ref "J1") (pin "A1B12") (pinfunction "GND_A1B12_A1B12") (pintype "passive"))
      (node (ref "J1") (pin "B1A12") (pinfunction "GND_B1A12_B1A12") (pintype "passive"))
      (node (ref "J1") (pin "S1") (pinfunction "SHIELD_1_S1") (pintype "passive"))
      (node (ref "J1") (pin "S2") (pinfunction "SHIELD_2_S2") (pintype "passive"))
      (node (ref "J1") (pin "S3") (pinfunction "SHIELD_3_S3") (pintype "passive"))
      (node (ref "J1") (pin "S4") (pinfunction "SHIELD_4_S4") (pintype "passive"))
      (node (ref "J2") (pin "A1B12") (pinfunction "GND_A1B12_A1B12") (pintype "passive"))
      (node (ref "J2") (pin "B1A12") (pinfunction "GND_B1A12_B1A12") (pintype "passive"))
      (node (ref "J2") (pin "S1") (pinfunction "SHIELD_1_S1") (pintype "passive"))
      (node (ref "J2") (pin "S2") (pinfunction "SHIELD_2_S2") (pintype "passive"))
      (node (ref "J2") (pin "S3") (pinfunction "SHIELD_3_S3") (pintype "passive"))
      (node (ref "J2") (pin "S4") (pinfunction "SHIELD_4_S4") (pintype "passive"))
      (node (ref "J3") (pin "22") (pinfunction "22_22") (pintype "passive"))
      (node (ref "J3") (pin "23") (pinfunction "23_23") (pintype "passive"))
      (node (ref "J4") (pin "2") (pinfunction "2_2") (pintype "passive"))
      (node (ref "J4") (pin "23") (pinfunction "23_23") (pintype "passive"))
      (node (ref "R11") (pin "2") (pinfunction "2_2") (pintype "passive"))
      (node (ref "R13") (pin "2") (pinfunction "2_2") (pintype "passive"))
      (node (ref "R14") (pin "2") (pinfunction "2_2") (pintype "passive"))
      (node (ref "R15") (pin "1") (pinfunction "1_1") (pintype "passive"))
      (node (ref "R17") (pin "2") (pinfunction "2_2") (pintype "passive"))
      (node (ref "R20") (pin "2") (pinfunction "2_2") (pintype "passive"))
      (node (ref "R28") (pin "1") (pinfunction "1_1") (pintype "passive"))
      (node (ref "SW1") (pin "3") (pinfunction "3_3") (pintype "passive"))
      (node (ref "SW2") (pin "3") (pinfunction "3_3") (pintype "passive"))
      (node (ref "U1") (pin "1") (pinfunction "GND-56_1") (pintype "passive"))
      (node (ref "U2") (pin "2") (pinfunction "GND_2") (pintype "passive"))
      (node (ref "U3") (pin "13") (pinfunction "GND-2_13") (pintype "passive"))
      (node (ref "U3") (pin "21") (pinfunction "GND-3_21") (pintype "passive"))
      (node (ref "U3") (pin "3") (pinfunction "GND-1_3") (pintype "passive"))
    )
    (net (code "64") (name "Net-(D7-Pad1)") (class "Default")
      (node (ref "D7") (pin "1") (pinfunction "1_1") (pintype "passive"))
      (node (ref "R21") (pin "2") (pinfunction "2_2") (pintype "passive"))
    )
    (net (code "65") (name "Net-(D8-Pad1)") (class "Default")
      (node (ref "D8") (pin "1") (pinfunction "1_1") (pintype "passive"))
      (node (ref "R26") (pin "1") (pinfunction "1_1") (pintype "passive"))
    )
    (net (code "66") (name "Net-(J1-CC1)") (class "Default")
      (node (ref "J1") (pin "A5") (pinfunction "CC1_A5") (pintype "passive"))
      (node (ref "R11") (pin "1") (pinfunction "1_1") (pintype "passive"))
    )
    (net (code "67") (name "Net-(J1-CC2)") (class "Default")
      (node (ref "J1") (pin "B5") (pinfunction "CC2_B5") (pintype "passive"))
      (node (ref "R14") (pin "1") (pinfunction "1_1") (pintype "passive"))
    )
    (net (code "68") (name "Net-(J2-CC1)") (class "Default")
      (node (ref "J2") (pin "A5") (pinfunction "CC1_A5") (pintype "passive"))
      (node (ref "R17") (pin "1") (pinfunction "1_1") (pintype "passive"))
    )
    (net (code "69") (name "Net-(J2-CC2)") (class "Default")
      (node (ref "J2") (pin "B5") (pinfunction "CC2_B5") (pintype "passive"))
      (node (ref "R20") (pin "1") (pinfunction "1_1") (pintype "passive"))
    )
    (net (code "70") (name "Net-(Q1-B)") (class "Default")
      (node (ref "Q1") (pin "1") (pinfunction "B_1") (pintype "passive"))
      (node (ref "R16") (pin "2") (pinfunction "2_2") (pintype "passive"))
    )
    (net (code "71") (name "Net-(Q2-B)") (class "Default")
      (node (ref "Q2") (pin "1") (pinfunction "B_1") (pintype "passive"))
      (node (ref "R4") (pin "2") (pinfunction "2_2") (pintype "passive"))
    )
    (net (code "72") (name "Net-(U2-CB)") (class "Default")
      (node (ref "C6") (pin "2") (pinfunction "2_2") (pintype "passive"))
      (node (ref "U2") (pin "1") (pinfunction "CB_1") (pintype "passive"))
    )
    (net (code "73") (name "Net-(U2-FB)") (class "Default")
      (node (ref "R27") (pin "1") (pinfunction "1_1") (pintype "passive"))
      (node (ref "R28") (pin "2") (pinfunction "2_2") (pintype "passive"))
      (node (ref "U2") (pin "3") (pinfunction "FB_3") (pintype "passive"))
    )
    (net (code "74") (name "Net-(U2-SW)") (class "Default")
      (node (ref "C6") (pin "1") (pinfunction "1_1") (pintype "passive"))
      (node (ref "L1") (pin "1") (pinfunction "1_1") (pintype "passive"))
      (node (ref "U2") (pin "6") (pinfunction "SW_6") (pintype "passive"))
    )
    (net (code "75") (name "Net-(U3-CBUS3)") (class "Default")
      (node (ref "R13") (pin "1") (pinfunction "1_1") (pintype "passive"))
      (node (ref "U3") (pin "16") (pinfunction "CBUS3_16") (pintype "passive"))
    )
    (net (code "76") (name "Net-(U3-~{RESET})") (class "Default")
      (node (ref "C7") (pin "2") (pinfunction "2_2") (pintype "passive"))
      (node (ref "R7") (pin "2") (pinfunction "2_2") (pintype "passive"))
      (node (ref "U3") (pin "11") (pinfunction "~{RESET}_11") (pintype "passive"))
    )
    (net (code "77") (name "unconnected-(J1-SBU1-PadA8)") (class "Default")
      (node (ref "J1") (pin "A8") (pinfunction "SBU1_A8") (pintype "passive+no_connect"))
    )
    (net (code "78") (name "unconnected-(J1-SBU2-PadB8)") (class "Default")
      (node (ref "J1") (pin "B8") (pinfunction "SBU2_B8") (pintype "passive+no_connect"))
    )
    (net (code "79") (name "unconnected-(J2-SBU1-PadA8)") (class "Default")
      (node (ref "J2") (pin "A8") (pinfunction "SBU1_A8") (pintype "passive+no_connect"))
    )
    (net (code "80") (name "unconnected-(J2-SBU2-PadB8)") (class "Default")
      (node (ref "J2") (pin "B8") (pinfunction "SBU2_B8") (pintype "passive+no_connect"))
    )
    (net (code "81") (name "unconnected-(J4-Pad24)") (class "Default")
      (node (ref "J4") (pin "24") (pinfunction "24_24") (pintype "passive"))
    )
    (net (code "82") (name "unconnected-(U3-CBUS0-Pad15)") (class "Default")
      (node (ref "U3") (pin "15") (pinfunction "CBUS0_15") (pintype "passive+no_connect"))
    )
    (net (code "83") (name "unconnected-(U3-CBUS1-Pad14)") (class "Default")
      (node (ref "U3") (pin "14") (pinfunction "CBUS1_14") (pintype "passive+no_connect"))
    )
    (net (code "84") (name "unconnected-(U3-~{CTS}-Pad6)") (class "Default")
      (node (ref "U3") (pin "6") (pinfunction "~{CTS}_6") (pintype "passive+no_connect"))
    )
    (net (code "85") (name "unconnected-(U3-~{DCD}-Pad5)") (class "Default")
      (node (ref "U3") (pin "5") (pinfunction "~{DCD}_5") (pintype "passive+no_connect"))
    )
    (net (code "86") (name "unconnected-(U3-~{DSR}-Pad4)") (class "Default")
      (node (ref "U3") (pin "4") (pinfunction "~{DSR}_4") (pintype "passive+no_connect"))
    )
    (net (code "87") (name "unconnected-(U3-~{RI}-Pad2)") (class "Default")
      (node (ref "U3") (pin "2") (pinfunction "~{RI}_2") (pintype "passive+no_connect"))
    )
  )
)
